# SNESModule_r1.net
KiCad netlist of a schematic drawn in EAGLE
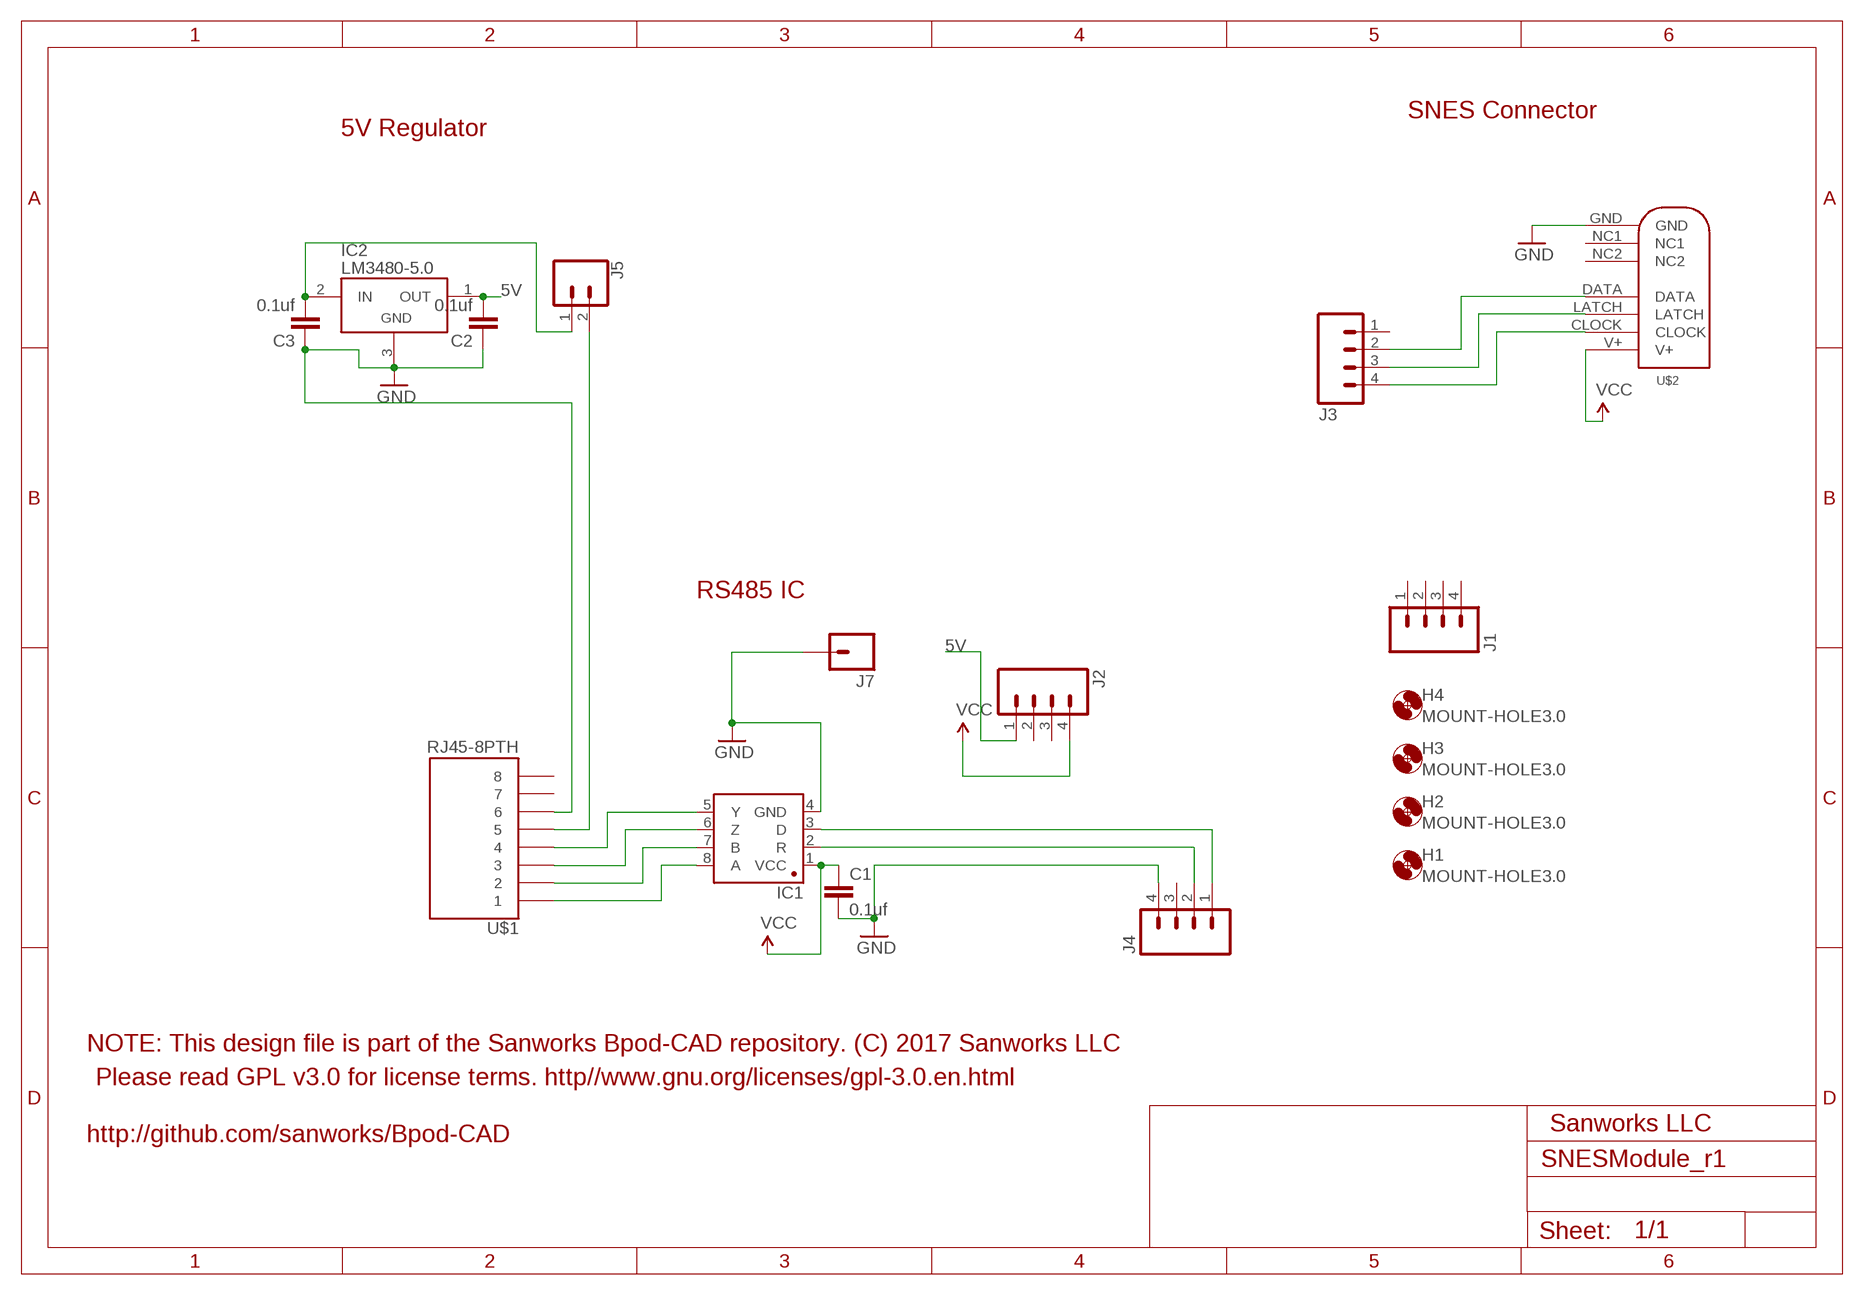
[diagram p0: schematic, sheet 1]

(export (version "E")
  (design (tool "Eeschema 10.0.6"))
  (components
    (comp (ref "C1")
      (value "0.1uf")
      (footprint "eagle-import:1206")
      (libsource (lib "eagle-import") (part "CAP1206"))
    )
    (comp (ref "C2")
      (value "0.1uf")
      (footprint "eagle-import:1206")
      (libsource (lib "eagle-import") (part "CAP1206"))
    )
    (comp (ref "C3")
      (value "0.1uf")
      (footprint "eagle-import:1206")
      (libsource (lib "eagle-import") (part "CAP1206"))
    )
    (comp (ref "H1")
      (value "MOUNT-HOLE3.0")
      (footprint "eagle-import:3,0")
      (libsource (lib "eagle-import") (part "MOUNT-HOLE3.0"))
    )
    (comp (ref "H2")
      (value "MOUNT-HOLE3.0")
      (footprint "eagle-import:3,0")
      (libsource (lib "eagle-import") (part "MOUNT-HOLE3.0"))
    )
    (comp (ref "H3")
      (value "MOUNT-HOLE3.0")
      (footprint "eagle-import:3,0")
      (libsource (lib "eagle-import") (part "MOUNT-HOLE3.0"))
    )
    (comp (ref "H4")
      (value "MOUNT-HOLE3.0")
      (footprint "eagle-import:3,0")
      (libsource (lib "eagle-import") (part "MOUNT-HOLE3.0"))
    )
    (comp (ref "IC1")
      (value "SN65HVD31DR")
      (footprint "eagle-import:SO08")
      (libsource (lib "eagle-import") (part "SN65HVD31DR"))
    )
    (comp (ref "IC2")
      (value "LM3480-5.0")
      (footprint "eagle-import:SOT-23-3")
      (libsource (lib "eagle-import") (part "LM3480-5.0"))
    )
    (comp (ref "J1")
      (value "M04PTH")
      (footprint "eagle-import:1X04")
      (libsource (lib "eagle-import") (part "M04PTH"))
    )
    (comp (ref "J2")
      (value "M04PTH")
      (footprint "eagle-import:1X04")
      (libsource (lib "eagle-import") (part "M04PTH"))
    )
    (comp (ref "J3")
      (value "M04PTH")
      (footprint "eagle-import:1X04")
      (libsource (lib "eagle-import") (part "M04PTH"))
    )
    (comp (ref "J4")
      (value "M04PTH")
      (footprint "eagle-import:1X04")
      (libsource (lib "eagle-import") (part "M04PTH"))
    )
    (comp (ref "J5")
      (value "CONN_02")
      (footprint "eagle-import:1X02")
      (libsource (lib "eagle-import") (part "CONN_02"))
    )
    (comp (ref "J7")
      (value "M01PTH")
      (footprint "eagle-import:1X01")
      (libsource (lib "eagle-import") (part "M01PTH"))
    )
    (comp (ref "U$1")
      (value "RJ45-8PTH")
      (footprint "eagle-import:RJ45-8")
      (libsource (lib "eagle-import") (part "RJ45-8PTH"))
    )
    (comp (ref "U$2")
      (value "SNES_CONNECTOR")
      (footprint "eagle-import:SNES_CONNECTOR")
      (libsource (lib "eagle-import") (part "SNES_CONNECTOR"))
    )
  )
  (nets
    (net (code "1") (name "/5V") (class "Default")
      (node (ref "C2") (pin "2") (pinfunction "2_2") (pintype "passive"))
      (node (ref "IC2") (pin "1") (pinfunction "OUT_1") (pintype "power_in"))
      (node (ref "J2") (pin "1") (pinfunction "1_1") (pintype "passive"))
    )
    (net (code "2") (name "GND") (class "Default")
      (node (ref "C1") (pin "2") (pinfunction "2_2") (pintype "passive"))
      (node (ref "C2") (pin "1") (pinfunction "1_1") (pintype "passive"))
      (node (ref "C3") (pin "1") (pinfunction "1_1") (pintype "passive"))
      (node (ref "IC1") (pin "4") (pinfunction "GND_4") (pintype "bidirectional"))
      (node (ref "IC2") (pin "3") (pinfunction "GND_3") (pintype "power_in"))
      (node (ref "J4") (pin "4") (pinfunction "4_4") (pintype "passive"))
      (node (ref "J7") (pin "1") (pinfunction "1_1") (pintype "passive"))
      (node (ref "U$1") (pin "6") (pinfunction "6_6") (pintype "bidirectional"))
      (node (ref "U$2") (pin "GND") (pinfunction "GND_GND") (pintype "passive"))
    )
    (net (code "3") (name "Net-(IC1-A)") (class "Default")
      (node (ref "IC1") (pin "8") (pinfunction "A_8") (pintype "bidirectional"))
      (node (ref "U$1") (pin "1") (pinfunction "1_1") (pintype "bidirectional"))
    )
    (net (code "4") (name "Net-(IC1-B)") (class "Default")
      (node (ref "IC1") (pin "7") (pinfunction "B_7") (pintype "bidirectional"))
      (node (ref "U$1") (pin "2") (pinfunction "2_2") (pintype "bidirectional"))
    )
    (net (code "5") (name "Net-(IC1-D)") (class "Default")
      (node (ref "IC1") (pin "3") (pinfunction "D_3") (pintype "bidirectional"))
      (node (ref "J4") (pin "1") (pinfunction "1_1") (pintype "passive"))
    )
    (net (code "6") (name "Net-(IC1-R)") (class "Default")
      (node (ref "IC1") (pin "2") (pinfunction "R_2") (pintype "bidirectional"))
      (node (ref "J4") (pin "2") (pinfunction "2_2") (pintype "passive"))
    )
    (net (code "7") (name "Net-(IC1-Y)") (class "Default")
      (node (ref "IC1") (pin "5") (pinfunction "Y_5") (pintype "bidirectional"))
      (node (ref "U$1") (pin "4") (pinfunction "4_4") (pintype "bidirectional"))
    )
    (net (code "8") (name "Net-(IC1-Z)") (class "Default")
      (node (ref "IC1") (pin "6") (pinfunction "Z_6") (pintype "bidirectional"))
      (node (ref "U$1") (pin "3") (pinfunction "3_3") (pintype "bidirectional"))
    )
    (net (code "9") (name "Net-(IC2-IN)") (class "Default")
      (node (ref "C3") (pin "2") (pinfunction "2_2") (pintype "passive"))
      (node (ref "IC2") (pin "2") (pinfunction "IN_2") (pintype "power_in"))
      (node (ref "J5") (pin "1") (pinfunction "1_1") (pintype "passive"))
    )
    (net (code "10") (name "Net-(J3-Pad2)") (class "Default")
      (node (ref "J3") (pin "2") (pinfunction "2_2") (pintype "passive"))
      (node (ref "U$2") (pin "DATA") (pinfunction "DATA_DATA") (pintype "passive"))
    )
    (net (code "11") (name "Net-(J3-Pad3)") (class "Default")
      (node (ref "J3") (pin "3") (pinfunction "3_3") (pintype "passive"))
      (node (ref "U$2") (pin "LATCH") (pinfunction "LATCH_LATCH") (pintype "passive"))
    )
    (net (code "12") (name "Net-(J3-Pad4)") (class "Default")
      (node (ref "J3") (pin "4") (pinfunction "4_4") (pintype "passive"))
      (node (ref "U$2") (pin "CLOCK") (pinfunction "CLOCK_CLOCK") (pintype "passive"))
    )
    (net (code "13") (name "Net-(J5-Pad2)") (class "Default")
      (node (ref "J5") (pin "2") (pinfunction "2_2") (pintype "passive"))
      (node (ref "U$1") (pin "5") (pinfunction "5_5") (pintype "bidirectional"))
    )
    (net (code "14") (name "VCC") (class "Default")
      (node (ref "C1") (pin "1") (pinfunction "1_1") (pintype "passive"))
      (node (ref "IC1") (pin "1") (pinfunction "VCC_1") (pintype "bidirectional"))
      (node (ref "J2") (pin "4") (pinfunction "4_4") (pintype "passive"))
      (node (ref "U$2") (pin "V+") (pinfunction "V+_V+") (pintype "passive"))
    )
    (net (code "15") (name "unconnected-(J1-Pad1)") (class "Default")
      (node (ref "J1") (pin "1") (pinfunction "1_1") (pintype "passive"))
    )
    (net (code "16") (name "unconnected-(J1-Pad2)") (class "Default")
      (node (ref "J1") (pin "2") (pinfunction "2_2") (pintype "passive"))
    )
    (net (code "17") (name "unconnected-(J1-Pad3)") (class "Default")
      (node (ref "J1") (pin "3") (pinfunction "3_3") (pintype "passive"))
    )
    (net (code "18") (name "unconnected-(J1-Pad4)") (class "Default")
      (node (ref "J1") (pin "4") (pinfunction "4_4") (pintype "passive"))
    )
    (net (code "19") (name "unconnected-(J2-Pad2)") (class "Default")
      (node (ref "J2") (pin "2") (pinfunction "2_2") (pintype "passive"))
    )
    (net (code "20") (name "unconnected-(J2-Pad3)") (class "Default")
      (node (ref "J2") (pin "3") (pinfunction "3_3") (pintype "passive"))
    )
    (net (code "21") (name "unconnected-(J3-Pad1)") (class "Default")
      (node (ref "J3") (pin "1") (pinfunction "1_1") (pintype "passive"))
    )
    (net (code "22") (name "unconnected-(J4-Pad3)") (class "Default")
      (node (ref "J4") (pin "3") (pinfunction "3_3") (pintype "passive"))
    )
    (net (code "23") (name "unconnected-(U$1-Pad7)") (class "Default")
      (node (ref "U$1") (pin "7") (pinfunction "7_7") (pintype "bidirectional"))
    )
    (net (code "24") (name "unconnected-(U$1-Pad8)") (class "Default")
      (node (ref "U$1") (pin "8") (pinfunction "8_8") (pintype "bidirectional"))
    )
    (net (code "25") (name "unconnected-(U$2-PadNC1)") (class "Default")
      (node (ref "U$2") (pin "NC1") (pinfunction "NC1_NC1") (pintype "passive"))
    )
    (net (code "26") (name "unconnected-(U$2-PadNC2)") (class "Default")
      (node (ref "U$2") (pin "NC2") (pinfunction "NC2_NC2") (pintype "passive"))
    )
  )
)
